# MAGI_sDuinoCore.net
KiCad netlist of a schematic drawn in Altium Designer
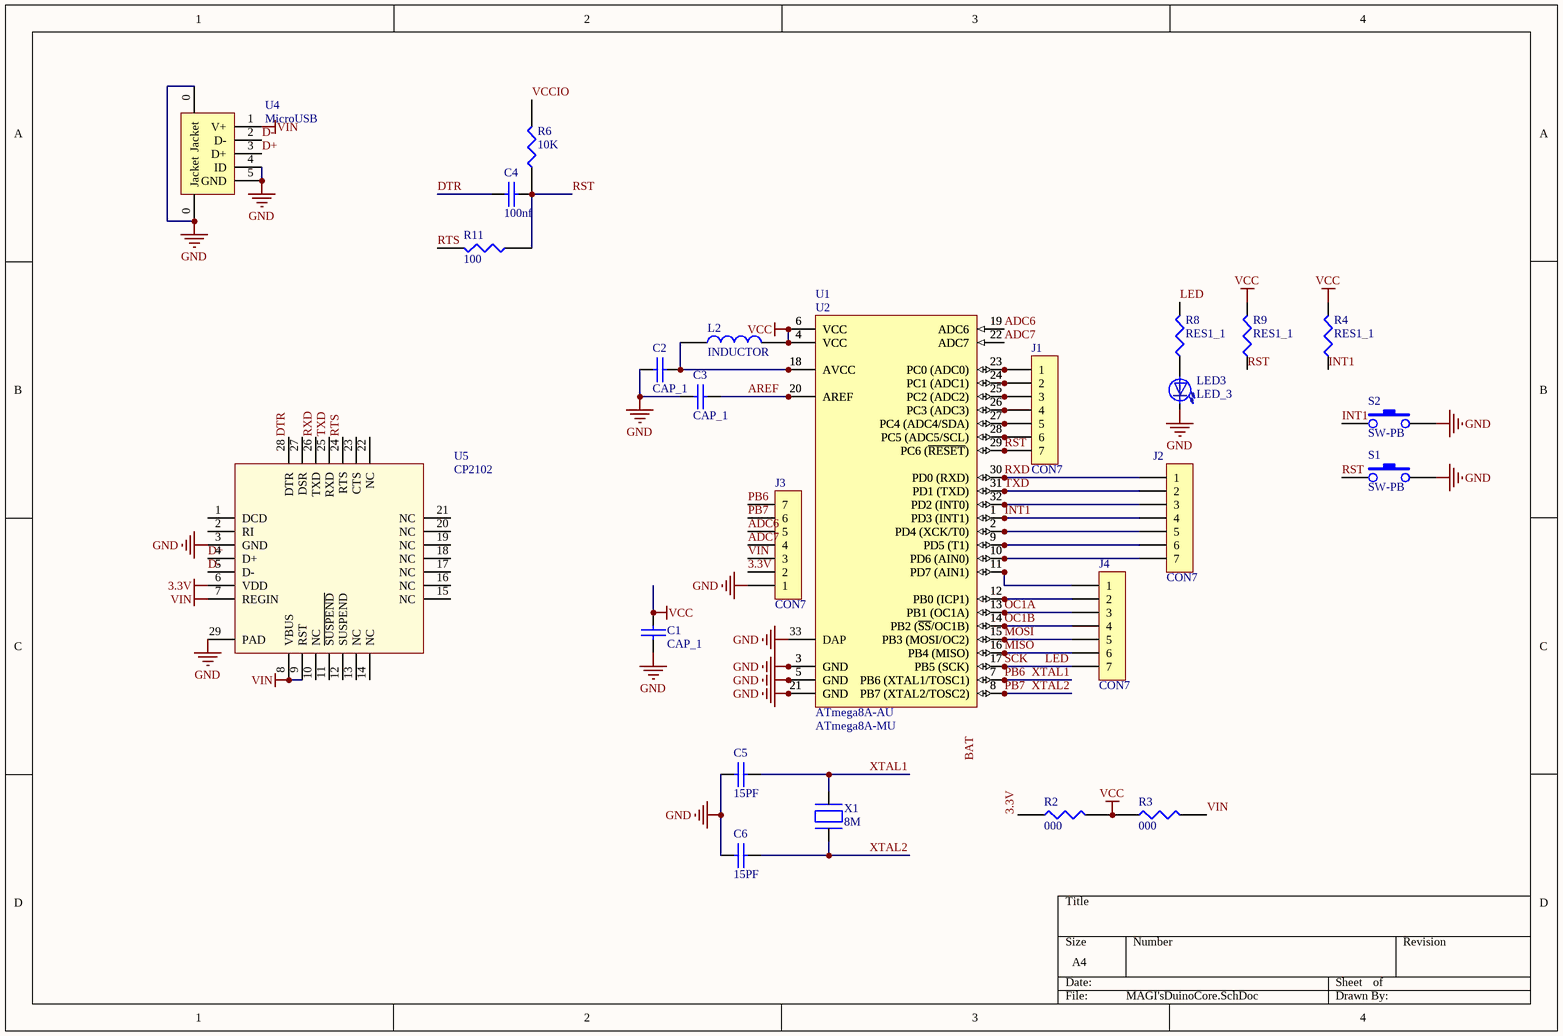
[diagram p0: MAGI'sDuinoCore.SchDoc]

(export (version "E")
  (design (tool "Eeschema 10.0.6"))
  (components
    (comp (ref "C1")
      (value "CAP_1")
      (footprint "1210")
      (description "Capacitor")
      (libsource (lib "电容器") (part "CAP_1"))
    )
    (comp (ref "C2")
      (value "CAP_1")
      (footprint "6-0805_N")
      (description "Capacitor")
      (libsource (lib "电容器") (part "CAP_1"))
    )
    (comp (ref "C3")
      (value "CAP_1")
      (footprint "6-0805_N")
      (description "Capacitor")
      (libsource (lib "电容器") (part "CAP_1"))
    )
    (comp (ref "C4")
      (value "100nf")
      (footprint "6-0805_n")
      (description "Capacitor")
      (libsource (lib "电容器") (part "CAP_1"))
    )
    (comp (ref "C5") (value "15PF") (footprint "6-0805_n") (libsource (lib "STM32") (part "CAP")))
    (comp (ref "C6") (value "15PF") (footprint "6-0805_n") (libsource (lib "STM32") (part "CAP")))
    (comp (ref "J1")
      (value "CON7")
      (footprint "CON7")
      (description "Connector")
      (libsource (lib "CON系列") (part "CON7"))
    )
    (comp (ref "J2")
      (value "CON7")
      (footprint "CON7")
      (description "Connector")
      (libsource (lib "CON系列") (part "CON7"))
    )
    (comp (ref "J3")
      (value "CON7")
      (footprint "CON7")
      (description "Connector")
      (libsource (lib "") (part "CON7_1"))
    )
    (comp (ref "J4")
      (value "CON7")
      (footprint "CON7")
      (description "Connector")
      (libsource (lib "CON系列") (part "CON7"))
    )
    (comp (ref "L2") (value "INDUCTOR") (footprint "14-1210") (libsource (lib "汇总") (part "INDUCTOR")))
    (comp (ref "LED3") (value "LED_3") (footprint "6-0805_N") (libsource (lib "二极管") (part "LED_3")))
    (comp (ref "R2") (value "000") (footprint "Jump") (libsource (lib "电阻器") (part "RES1")))
    (comp (ref "R3") (value "000") (footprint "Jump") (libsource (lib "电阻器") (part "RES1")))
    (comp (ref "R4") (value "RES1_1") (footprint "6-0805_N") (libsource (lib "电阻器") (part "RES1_1")))
    (comp (ref "R6") (value "10K") (footprint "6-0805_N") (libsource (lib "电阻器") (part "RES1")))
    (comp (ref "R8") (value "RES1_1") (footprint "6-0805_N") (libsource (lib "电阻器") (part "RES1_1")))
    (comp (ref "R9") (value "RES1_1") (footprint "6-0805_N") (libsource (lib "电阻器") (part "RES1_1")))
    (comp (ref "R11") (value "100") (footprint "6-0805_N") (libsource (lib "电阻器") (part "RES1")))
    (comp (ref "S1") (value "SW-PB") (footprint "SKRELGE010") (libsource (lib "手动开关") (part "SW-PB")))
    (comp (ref "S2") (value "SW-PB") (footprint "SKRELGE010") (libsource (lib "手动开关") (part "SW-PB")))
    (comp (ref "U1")
      (value "ATmega8A-AU")
      (footprint "32A_N")
      (fields (field (name "PUBLISHER") "Altium Limited"))
      (libsource (lib "Atmel Microcontroller 8-Bit megaAVR") (part "ATmega8A-AU"))
    )
    (comp (ref "U2")
      (value "ATmega8A-MU")
      (footprint "32M1-A_N")
      (fields (field (name "PUBLISHER") "Altium Limited"))
      (libsource (lib "Atmel Microcontroller 8-Bit megaAVR") (part "ATmega8A-MU"))
    )
    (comp (ref "U4") (value "MicroUSB") (footprint "MicroUSB-B") (libsource (lib "USB") (part "MicroUSB2.0")))
    (comp (ref "U5") (value "CP2102") (footprint "CP2102") (libsource (lib "LogicIC") (part "CP2102")))
    (comp (ref "X1") (value "8M") (footprint "5032") (libsource (lib "STM32") (part "CRYSTAL")))
  )
  (nets
    (net (code "1") (name "/ADC6") (class "Default")
      (node (ref "J3") (pin "5") (pinfunction "5_5") (pintype "passive"))
      (node (ref "U1") (pin "19") (pinfunction "ADC6_19") (pintype "input"))
      (node (ref "U2") (pin "19") (pinfunction "ADC6_19") (pintype "input"))
    )
    (net (code "2") (name "/ADC7") (class "Default")
      (node (ref "J3") (pin "4") (pinfunction "4_4") (pintype "passive"))
      (node (ref "U1") (pin "22") (pinfunction "ADC7_22") (pintype "input"))
      (node (ref "U2") (pin "22") (pinfunction "ADC7_22") (pintype "input"))
    )
    (net (code "3") (name "/AREF") (class "Default")
      (node (ref "C3") (pin "2") (pinfunction "2_2") (pintype "passive"))
      (node (ref "U1") (pin "20") (pinfunction "AREF_20") (pintype "power_in"))
      (node (ref "U2") (pin "20") (pinfunction "AREF_20") (pintype "power_in"))
    )
    (net (code "5") (name "/D+") (class "Default")
      (node (ref "U4") (pin "3") (pinfunction "D+_3") (pintype "passive"))
      (node (ref "U5") (pin "4") (pinfunction "D+_4") (pintype "passive"))
    )
    (net (code "6") (name "/D-") (class "Default")
      (node (ref "U4") (pin "2") (pinfunction "D-_2") (pintype "passive"))
      (node (ref "U5") (pin "5") (pinfunction "D-_5") (pintype "passive"))
    )
    (net (code "7") (name "/DTR") (class "Default")
      (node (ref "C4") (pin "1") (pinfunction "1_1") (pintype "passive"))
      (node (ref "U5") (pin "28") (pinfunction "DTR_28") (pintype "passive"))
    )
    (net (code "8") (name "/INT1") (class "Default")
      (node (ref "J2") (pin "4") (pinfunction "4_4") (pintype "passive"))
      (node (ref "R4") (pin "1") (pinfunction "1_1") (pintype "passive"))
      (node (ref "S2") (pin "1") (pinfunction "1_1") (pintype "passive"))
      (node (ref "U1") (pin "1") (pinfunction "PD3_(INT1)_1") (pintype "bidirectional"))
      (node (ref "U2") (pin "1") (pinfunction "PD3_(INT1)_1") (pintype "bidirectional"))
    )
    (net (code "9") (name "/LED") (class "Default")
      (node (ref "J4") (pin "7") (pinfunction "7_7") (pintype "passive"))
      (node (ref "R8") (pin "2") (pinfunction "2_2") (pintype "passive"))
      (node (ref "U1") (pin "17") (pinfunction "PB5_(SCK)_17") (pintype "bidirectional"))
      (node (ref "U2") (pin "17") (pinfunction "PB5_(SCK)_17") (pintype "bidirectional"))
    )
    (net (code "10") (name "/MISO") (class "Default")
      (node (ref "J4") (pin "6") (pinfunction "6_6") (pintype "passive"))
      (node (ref "U1") (pin "16") (pinfunction "PB4_(MISO)_16") (pintype "bidirectional"))
      (node (ref "U2") (pin "16") (pinfunction "PB4_(MISO)_16") (pintype "bidirectional"))
    )
    (net (code "11") (name "/MOSI") (class "Default")
      (node (ref "J4") (pin "5") (pinfunction "5_5") (pintype "passive"))
      (node (ref "U1") (pin "15") (pinfunction "PB3_(MOSI/OC2)_15") (pintype "bidirectional"))
      (node (ref "U2") (pin "15") (pinfunction "PB3_(MOSI/OC2)_15") (pintype "bidirectional"))
    )
    (net (code "12") (name "/OC1A") (class "Default")
      (node (ref "J4") (pin "3") (pinfunction "3_3") (pintype "passive"))
      (node (ref "U1") (pin "13") (pinfunction "PB1_(OC1A)_13") (pintype "bidirectional"))
      (node (ref "U2") (pin "13") (pinfunction "PB1_(OC1A)_13") (pintype "bidirectional"))
    )
    (net (code "13") (name "/OC1B") (class "Default")
      (node (ref "J4") (pin "4") (pinfunction "4_4") (pintype "passive"))
      (node (ref "U1") (pin "14") (pinfunction "PB2_(~{SS}/OC1B)_14") (pintype "bidirectional"))
      (node (ref "U2") (pin "14") (pinfunction "PB2_(~{SS}/OC1B)_14") (pintype "bidirectional"))
    )
    (net (code "14") (name "/PB6") (class "Default")
      (node (ref "C5") (pin "2") (pinfunction "2_2") (pintype "passive"))
      (node (ref "J3") (pin "7") (pinfunction "7_7") (pintype "passive"))
      (node (ref "U1") (pin "7") (pinfunction "PB6_(XTAL1/TOSC1)_7") (pintype "bidirectional"))
      (node (ref "U2") (pin "7") (pinfunction "PB6_(XTAL1/TOSC1)_7") (pintype "bidirectional"))
      (node (ref "X1") (pin "1") (pinfunction "1_1") (pintype "passive"))
    )
    (net (code "15") (name "/PB7") (class "Default")
      (node (ref "C6") (pin "2") (pinfunction "2_2") (pintype "passive"))
      (node (ref "J3") (pin "6") (pinfunction "6_6") (pintype "passive"))
      (node (ref "U1") (pin "8") (pinfunction "PB7_(XTAL2/TOSC2)_8") (pintype "bidirectional"))
      (node (ref "U2") (pin "8") (pinfunction "PB7_(XTAL2/TOSC2)_8") (pintype "bidirectional"))
      (node (ref "X1") (pin "2") (pinfunction "2_2") (pintype "passive"))
    )
    (net (code "16") (name "/RST") (class "Default")
      (node (ref "C4") (pin "2") (pinfunction "2_2") (pintype "passive"))
      (node (ref "J1") (pin "7") (pinfunction "7_7") (pintype "passive"))
      (node (ref "R11") (pin "1") (pinfunction "1_1") (pintype "passive"))
      (node (ref "R6") (pin "1") (pinfunction "1_1") (pintype "passive"))
      (node (ref "R9") (pin "1") (pinfunction "1_1") (pintype "passive"))
      (node (ref "S1") (pin "1") (pinfunction "1_1") (pintype "passive"))
      (node (ref "U1") (pin "29") (pinfunction "PC6_(~{RESET})_29") (pintype "bidirectional"))
      (node (ref "U2") (pin "29") (pinfunction "PC6_(~{RESET})_29") (pintype "bidirectional"))
    )
    (net (code "17") (name "/RTS") (class "Default")
      (node (ref "R11") (pin "2") (pinfunction "2_2") (pintype "passive"))
      (node (ref "U5") (pin "24") (pinfunction "RTS_24") (pintype "passive"))
    )
    (net (code "18") (name "/RXD") (class "Default")
      (node (ref "J2") (pin "1") (pinfunction "1_1") (pintype "passive"))
      (node (ref "U1") (pin "30") (pinfunction "PD0_(RXD)_30") (pintype "bidirectional"))
      (node (ref "U2") (pin "30") (pinfunction "PD0_(RXD)_30") (pintype "bidirectional"))
      (node (ref "U5") (pin "26") (pinfunction "TXD_26") (pintype "passive"))
    )
    (net (code "19") (name "/TXD") (class "Default")
      (node (ref "J2") (pin "2") (pinfunction "2_2") (pintype "passive"))
      (node (ref "U1") (pin "31") (pinfunction "PD1_(TXD)_31") (pintype "bidirectional"))
      (node (ref "U2") (pin "31") (pinfunction "PD1_(TXD)_31") (pintype "bidirectional"))
      (node (ref "U5") (pin "25") (pinfunction "RXD_25") (pintype "passive"))
    )
    (net (code "20") (name "/VCCIO") (class "Default")
      (node (ref "R6") (pin "2") (pinfunction "2_2") (pintype "passive"))
    )
    (net (code "21") (name "3.3V") (class "Default")
      (node (ref "J3") (pin "2") (pinfunction "2_2") (pintype "passive"))
      (node (ref "R2") (pin "1") (pinfunction "1_1") (pintype "passive"))
      (node (ref "U5") (pin "6") (pinfunction "VDD_6") (pintype "passive"))
    )
    (net (code "22") (name "GND") (class "Default")
      (node (ref "C1") (pin "1") (pinfunction "1_1") (pintype "passive"))
      (node (ref "C2") (pin "1") (pinfunction "1_1") (pintype "passive"))
      (node (ref "C3") (pin "1") (pinfunction "1_1") (pintype "passive"))
      (node (ref "C5") (pin "1") (pinfunction "1_1") (pintype "passive"))
      (node (ref "C6") (pin "1") (pinfunction "1_1") (pintype "passive"))
      (node (ref "J3") (pin "1") (pinfunction "1_1") (pintype "passive"))
      (node (ref "LED3") (pin "2") (pinfunction "K_2") (pintype "passive"))
      (node (ref "S1") (pin "2") (pinfunction "2_2") (pintype "passive"))
      (node (ref "S2") (pin "2") (pinfunction "2_2") (pintype "passive"))
      (node (ref "U1") (pin "21") (pinfunction "GND_21") (pintype "power_in"))
      (node (ref "U1") (pin "3") (pinfunction "GND_3") (pintype "power_in"))
      (node (ref "U1") (pin "5") (pinfunction "GND_5") (pintype "power_in"))
      (node (ref "U2") (pin "21") (pinfunction "GND_21") (pintype "power_in"))
      (node (ref "U2") (pin "3") (pinfunction "GND_3") (pintype "power_in"))
      (node (ref "U2") (pin "33") (pinfunction "DAP_33") (pintype "power_in"))
      (node (ref "U2") (pin "5") (pinfunction "GND_5") (pintype "power_in"))
      (node (ref "U4") (pin "0") (pinfunction "Jacket_0") (pintype "passive"))
      (node (ref "U4") (pin "4") (pinfunction "ID_4") (pintype "passive"))
      (node (ref "U4") (pin "5") (pinfunction "GND_5") (pintype "passive"))
      (node (ref "U5") (pin "29") (pinfunction "PAD_29") (pintype "passive"))
      (node (ref "U5") (pin "3") (pinfunction "GND_3") (pintype "passive"))
    )
    (net (code "23") (name "Net-(LED3-A)") (class "Default")
      (node (ref "LED3") (pin "1") (pinfunction "A_1") (pintype "passive"))
      (node (ref "R8") (pin "1") (pinfunction "1_1") (pintype "passive"))
    )
    (net (code "24") (name "Net-(U1-AVCC)") (class "Default")
      (node (ref "C2") (pin "2") (pinfunction "2_2") (pintype "passive"))
      (node (ref "L2") (pin "1") (pinfunction "1_1") (pintype "passive"))
      (node (ref "U1") (pin "18") (pinfunction "AVCC_18") (pintype "power_in"))
      (node (ref "U2") (pin "18") (pinfunction "AVCC_18") (pintype "power_in"))
    )
    (net (code "25") (name "Net-(U1-PB0_(ICP1))") (class "Default")
      (node (ref "J4") (pin "2") (pinfunction "2_2") (pintype "passive"))
      (node (ref "U1") (pin "12") (pinfunction "PB0_(ICP1)_12") (pintype "bidirectional"))
      (node (ref "U2") (pin "12") (pinfunction "PB0_(ICP1)_12") (pintype "bidirectional"))
    )
    (net (code "26") (name "Net-(U1-PC0_(ADC0))") (class "Default")
      (node (ref "J1") (pin "1") (pinfunction "1_1") (pintype "passive"))
      (node (ref "U1") (pin "23") (pinfunction "PC0_(ADC0)_23") (pintype "bidirectional"))
      (node (ref "U2") (pin "23") (pinfunction "PC0_(ADC0)_23") (pintype "bidirectional"))
    )
    (net (code "27") (name "Net-(U1-PC1_(ADC1))") (class "Default")
      (node (ref "J1") (pin "2") (pinfunction "2_2") (pintype "passive"))
      (node (ref "U1") (pin "24") (pinfunction "PC1_(ADC1)_24") (pintype "bidirectional"))
      (node (ref "U2") (pin "24") (pinfunction "PC1_(ADC1)_24") (pintype "bidirectional"))
    )
    (net (code "28") (name "Net-(U1-PC2_(ADC2))") (class "Default")
      (node (ref "J1") (pin "3") (pinfunction "3_3") (pintype "passive"))
      (node (ref "U1") (pin "25") (pinfunction "PC2_(ADC2)_25") (pintype "bidirectional"))
      (node (ref "U2") (pin "25") (pinfunction "PC2_(ADC2)_25") (pintype "bidirectional"))
    )
    (net (code "29") (name "Net-(U1-PC3_(ADC3))") (class "Default")
      (node (ref "J1") (pin "4") (pinfunction "4_4") (pintype "passive"))
      (node (ref "U1") (pin "26") (pinfunction "PC3_(ADC3)_26") (pintype "bidirectional"))
      (node (ref "U2") (pin "26") (pinfunction "PC3_(ADC3)_26") (pintype "bidirectional"))
    )
    (net (code "30") (name "Net-(U1-PC4_(ADC4{slash}SDA))") (class "Default")
      (node (ref "J1") (pin "5") (pinfunction "5_5") (pintype "passive"))
      (node (ref "U1") (pin "27") (pinfunction "PC4_(ADC4/SDA)_27") (pintype "bidirectional"))
      (node (ref "U2") (pin "27") (pinfunction "PC4_(ADC4/SDA)_27") (pintype "bidirectional"))
    )
    (net (code "31") (name "Net-(U1-PC5_(ADC5{slash}SCL))") (class "Default")
      (node (ref "J1") (pin "6") (pinfunction "6_6") (pintype "passive"))
      (node (ref "U1") (pin "28") (pinfunction "PC5_(ADC5/SCL)_28") (pintype "bidirectional"))
      (node (ref "U2") (pin "28") (pinfunction "PC5_(ADC5/SCL)_28") (pintype "bidirectional"))
    )
    (net (code "32") (name "Net-(U1-PD2_(INT0))") (class "Default")
      (node (ref "J2") (pin "3") (pinfunction "3_3") (pintype "passive"))
      (node (ref "U1") (pin "32") (pinfunction "PD2_(INT0)_32") (pintype "bidirectional"))
      (node (ref "U2") (pin "32") (pinfunction "PD2_(INT0)_32") (pintype "bidirectional"))
    )
    (net (code "33") (name "Net-(U1-PD4_(XCK{slash}T0))") (class "Default")
      (node (ref "J2") (pin "5") (pinfunction "5_5") (pintype "passive"))
      (node (ref "U1") (pin "2") (pinfunction "PD4_(XCK/T0)_2") (pintype "bidirectional"))
      (node (ref "U2") (pin "2") (pinfunction "PD4_(XCK/T0)_2") (pintype "bidirectional"))
    )
    (net (code "34") (name "Net-(U1-PD5_(T1))") (class "Default")
      (node (ref "J2") (pin "6") (pinfunction "6_6") (pintype "passive"))
      (node (ref "U1") (pin "9") (pinfunction "PD5_(T1)_9") (pintype "bidirectional"))
      (node (ref "U2") (pin "9") (pinfunction "PD5_(T1)_9") (pintype "bidirectional"))
    )
    (net (code "35") (name "Net-(U1-PD6_(AIN0))") (class "Default")
      (node (ref "J2") (pin "7") (pinfunction "7_7") (pintype "passive"))
      (node (ref "U1") (pin "10") (pinfunction "PD6_(AIN0)_10") (pintype "bidirectional"))
      (node (ref "U2") (pin "10") (pinfunction "PD6_(AIN0)_10") (pintype "bidirectional"))
    )
    (net (code "36") (name "Net-(U1-PD7_(AIN1))") (class "Default")
      (node (ref "J4") (pin "1") (pinfunction "1_1") (pintype "passive"))
      (node (ref "U1") (pin "11") (pinfunction "PD7_(AIN1)_11") (pintype "bidirectional"))
      (node (ref "U2") (pin "11") (pinfunction "PD7_(AIN1)_11") (pintype "bidirectional"))
    )
    (net (code "37") (name "VCC") (class "Default")
      (node (ref "C1") (pin "2") (pinfunction "2_2") (pintype "passive"))
      (node (ref "L2") (pin "2") (pinfunction "2_2") (pintype "passive"))
      (node (ref "R2") (pin "2") (pinfunction "2_2") (pintype "passive"))
      (node (ref "R3") (pin "1") (pinfunction "1_1") (pintype "passive"))
      (node (ref "R4") (pin "2") (pinfunction "2_2") (pintype "passive"))
      (node (ref "R9") (pin "2") (pinfunction "2_2") (pintype "passive"))
      (node (ref "U1") (pin "4") (pinfunction "VCC_4") (pintype "power_in"))
      (node (ref "U1") (pin "6") (pinfunction "VCC_6") (pintype "power_in"))
      (node (ref "U2") (pin "4") (pinfunction "VCC_4") (pintype "power_in"))
      (node (ref "U2") (pin "6") (pinfunction "VCC_6") (pintype "power_in"))
    )
    (net (code "38") (name "VIN") (class "Default")
      (node (ref "J3") (pin "3") (pinfunction "3_3") (pintype "passive"))
      (node (ref "R3") (pin "2") (pinfunction "2_2") (pintype "passive"))
      (node (ref "U4") (pin "1") (pinfunction "V+_1") (pintype "passive"))
      (node (ref "U5") (pin "7") (pinfunction "REGIN_7") (pintype "passive"))
      (node (ref "U5") (pin "8") (pinfunction "VBUS_8") (pintype "passive"))
      (node (ref "U5") (pin "9") (pinfunction "RST_9") (pintype "passive"))
    )
    (net (code "39") (name "unconnected-(U5-CTS-Pad23)") (class "Default")
      (node (ref "U5") (pin "23") (pinfunction "CTS_23") (pintype "passive"))
    )
    (net (code "40") (name "unconnected-(U5-DCD-Pad1)") (class "Default")
      (node (ref "U5") (pin "1") (pinfunction "DCD_1") (pintype "passive"))
    )
    (net (code "41") (name "unconnected-(U5-DSR-Pad27)") (class "Default")
      (node (ref "U5") (pin "27") (pinfunction "DSR_27") (pintype "passive"))
    )
    (net (code "42") (name "unconnected-(U5-NC-Pad10)") (class "Default")
      (node (ref "U5") (pin "10") (pinfunction "NC_10") (pintype "passive"))
    )
    (net (code "43") (name "unconnected-(U5-NC-Pad13)") (class "Default")
      (node (ref "U5") (pin "13") (pinfunction "NC_13") (pintype "passive"))
    )
    (net (code "44") (name "unconnected-(U5-NC-Pad14)") (class "Default")
      (node (ref "U5") (pin "14") (pinfunction "NC_14") (pintype "passive"))
    )
    (net (code "45") (name "unconnected-(U5-NC-Pad15)") (class "Default")
      (node (ref "U5") (pin "15") (pinfunction "NC_15") (pintype "passive"))
    )
    (net (code "46") (name "unconnected-(U5-NC-Pad16)") (class "Default")
      (node (ref "U5") (pin "16") (pinfunction "NC_16") (pintype "passive"))
    )
    (net (code "47") (name "unconnected-(U5-NC-Pad17)") (class "Default")
      (node (ref "U5") (pin "17") (pinfunction "NC_17") (pintype "passive"))
    )
    (net (code "48") (name "unconnected-(U5-NC-Pad18)") (class "Default")
      (node (ref "U5") (pin "18") (pinfunction "NC_18") (pintype "passive"))
    )
    (net (code "49") (name "unconnected-(U5-NC-Pad19)") (class "Default")
      (node (ref "U5") (pin "19") (pinfunction "NC_19") (pintype "passive"))
    )
    (net (code "50") (name "unconnected-(U5-NC-Pad20)") (class "Default")
      (node (ref "U5") (pin "20") (pinfunction "NC_20") (pintype "passive"))
    )
    (net (code "51") (name "unconnected-(U5-NC-Pad21)") (class "Default")
      (node (ref "U5") (pin "21") (pinfunction "NC_21") (pintype "passive"))
    )
    (net (code "52") (name "unconnected-(U5-NC-Pad22)") (class "Default")
      (node (ref "U5") (pin "22") (pinfunction "NC_22") (pintype "passive"))
    )
    (net (code "53") (name "unconnected-(U5-RI-Pad2)") (class "Default")
      (node (ref "U5") (pin "2") (pinfunction "RI_2") (pintype "passive"))
    )
    (net (code "54") (name "unconnected-(U5-SUSPEND-Pad12)") (class "Default")
      (node (ref "U5") (pin "12") (pinfunction "SUSPEND_12") (pintype "passive"))
    )
    (net (code "55") (name "unconnected-(U5-~{SUSPEND}-Pad11)") (class "Default")
      (node (ref "U5") (pin "11") (pinfunction "~{SUSPEND}_11") (pintype "passive"))
    )
  )
)
